# 3__schdoc.net
KiCad netlist of a schematic drawn in Altium Designer
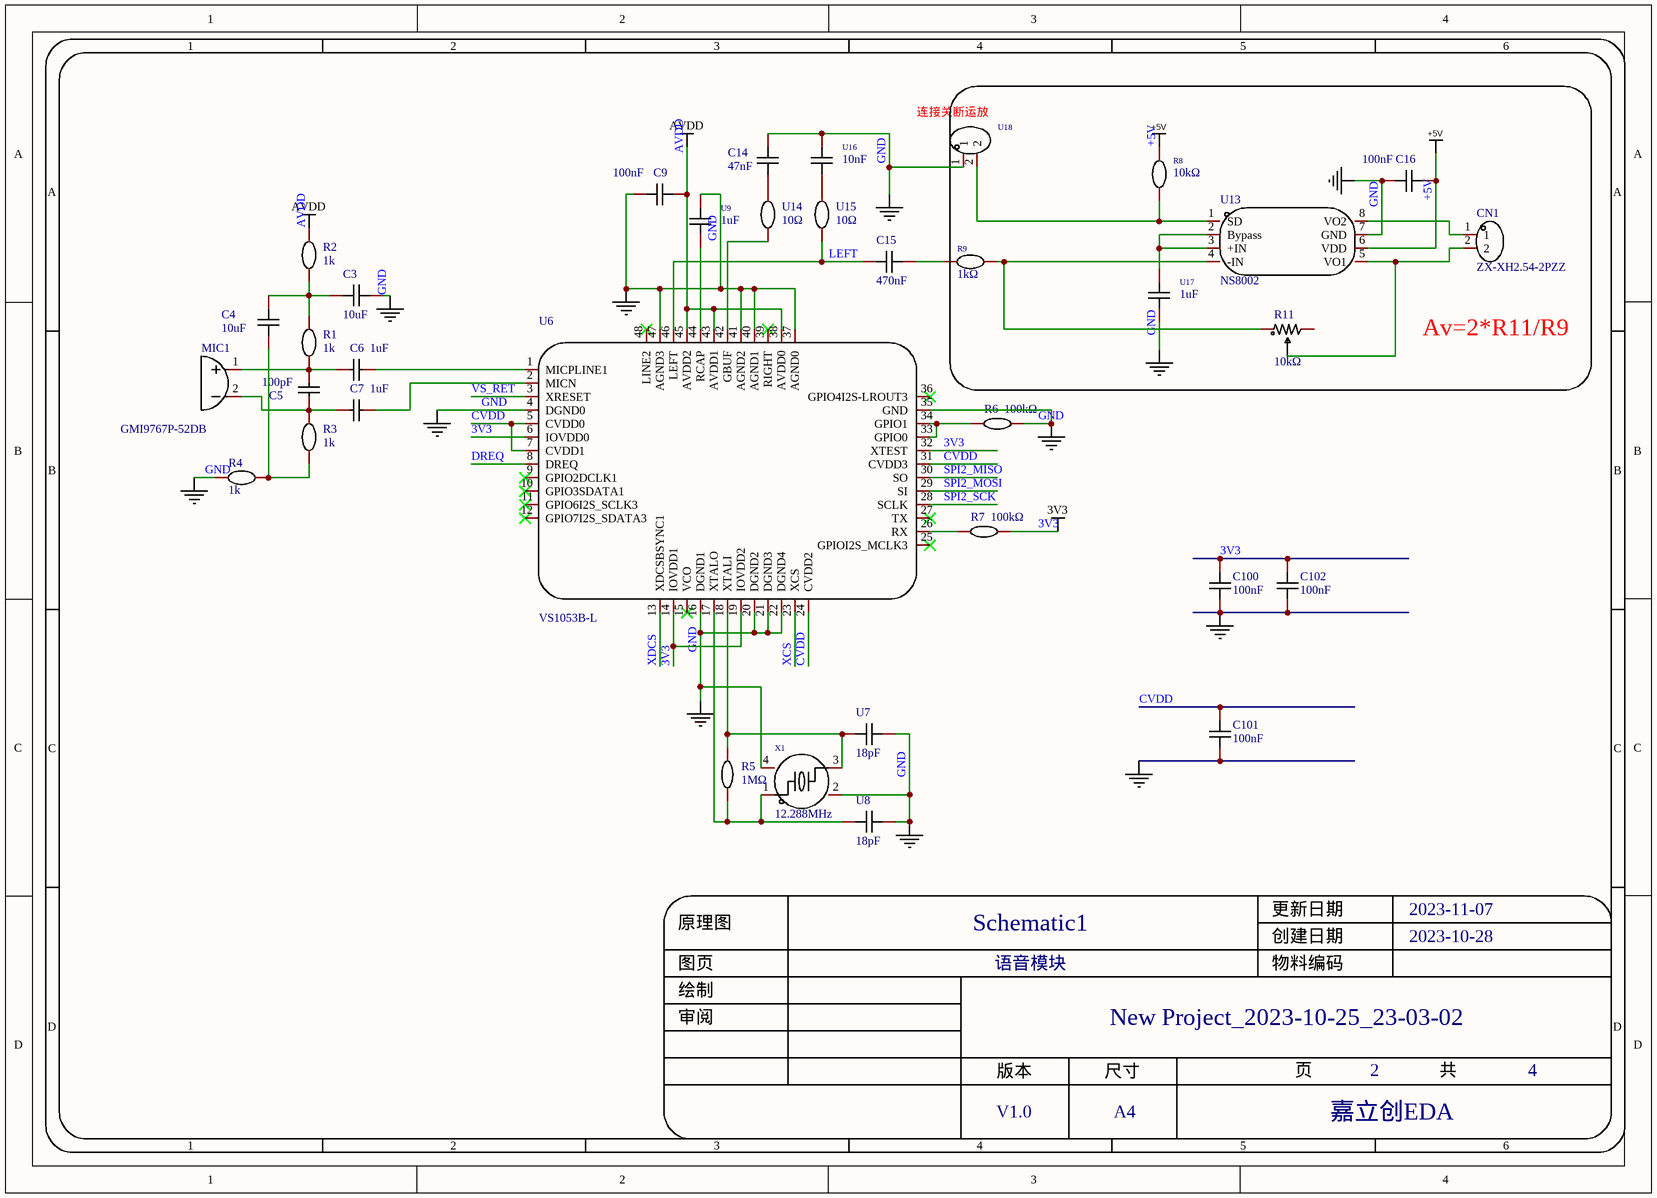
[diagram p0: 3_语音模块.schdoc.schdoc]

(export (version "E")
  (design (tool "Eeschema 10.0.6"))
  (components
    (comp (ref "C3")
      (value "10uF")
      (footprint "C0603")
      (description "容值:10uF;精度:±20%;额定电压:25V;材质(温度系数):X5R;")
      (fields
        (field (name "NAME") "10uF")
        (field (name "MANUFACTURER") "SAMSUNG(三星)")
        (field (name "MANUFACTURER PART") "CL10A106MA8NRNC")
      )
      (libsource (lib "altium-import") (part "root_0_CL10A106MA8NRNC_"))
    )
    (comp (ref "C4")
      (value "10uF")
      (footprint "C0603")
      (description "容值:10uF;精度:±20%;额定电压:25V;材质(温度系数):X5R;")
      (fields
        (field (name "NAME") "10uF")
        (field (name "MANUFACTURER") "SAMSUNG(三星)")
        (field (name "MANUFACTURER PART") "CL10A106MA8NRNC")
      )
      (libsource (lib "altium-import") (part "root_1_CL10A106MA8NRNC_"))
    )
    (comp (ref "C5")
      (value "100pF")
      (footprint "C0603")
      (description "容值:100pF;精度:±5%;额定电压:50V;材质(温度系数):C0G;")
      (fields
        (field (name "NAME") "100pF")
        (field (name "MANUFACTURER") "SAMSUNG(三星)")
        (field (name "MANUFACTURER PART") "CL10C101JB8NNNC")
      )
      (libsource (lib "altium-import") (part "root_1_CL10C101JB8NNNC_"))
    )
    (comp (ref "C6")
      (value "1uF")
      (footprint "C0603")
      (description "容值:1uF;精度:±10%;额定电压:50V;材质(温度系数):X5R;")
      (fields
        (field (name "NAME") "1uF")
        (field (name "MANUFACTURER") "SAMSUNG(三星)")
        (field (name "MANUFACTURER PART") "CL10A105KB8NNNC")
      )
      (libsource (lib "altium-import") (part "root_0_CL10A105KB8NNNC_"))
    )
    (comp (ref "C7")
      (value "1uF")
      (footprint "C0603")
      (description "容值:1uF;精度:±10%;额定电压:50V;材质(温度系数):X5R;")
      (fields
        (field (name "NAME") "1uF")
        (field (name "MANUFACTURER") "SAMSUNG(三星)")
        (field (name "MANUFACTURER PART") "CL10A105KB8NNNC")
      )
      (libsource (lib "altium-import") (part "root_0_CL10A105KB8NNNC_"))
    )
    (comp (ref "C9")
      (value "100nF")
      (footprint "C0603")
      (description "容值:100nF;精度:±20%;额定电压:50V;材质(温度系数):X8R;")
      (fields
        (field (name "NAME") "100nF")
        (field (name "MANUFACTURER") "TDK")
        (field (name "MANUFACTURER PART") "CGA3E3X8R1H104M080AE")
      )
      (libsource (lib "altium-import") (part "root_2_CGA3E3X8R1H104M080AE_"))
    )
    (comp (ref "C14")
      (value "47nF")
      (footprint "C0603")
      (description "容值:47nF;额定电压:50V;材质(温度系数):X8R;")
      (fields
        (field (name "NAME") "47nF")
        (field (name "MANUFACTURER") "TDK")
        (field (name "MANUFACTURER PART") "C1608X8R1H473K080AA")
      )
      (libsource (lib "altium-import") (part "root_1_C1608X8R1H473K080AA_"))
    )
    (comp (ref "C15")
      (value "470nF")
      (footprint "C0805")
      (description "容值:470nF;精度:±10%;额定电压:100V;材质(温度系数):X7R;")
      (fields
        (field (name "NAME") "470nF")
        (field (name "MANUFACTURER") "YAGEO(国巨)")
        (field (name "MANUFACTURER PART") "CC0805KKX7R0BB474")
      )
      (libsource (lib "altium-import") (part "root_0_CC0805KKX7R0BB474_"))
    )
    (comp (ref "C16")
      (value "100nF")
      (footprint "C0603")
      (description "容值:100nF;精度:±20%;额定电压:50V;材质(温度系数):X8R;")
      (fields
        (field (name "NAME") "100nF")
        (field (name "MANUFACTURER") "TDK")
        (field (name "MANUFACTURER PART") "CGA3E3X8R1H104M080AE")
      )
      (libsource (lib "altium-import") (part "root_2_CGA3E3X8R1H104M080AE_"))
    )
    (comp (ref "C100")
      (value "100nF")
      (footprint "C0603")
      (description "容值:100nF;精度:±20%;额定电压:50V;材质(温度系数):X8R;")
      (fields
        (field (name "NAME") "100nF")
        (field (name "MANUFACTURER") "TDK")
        (field (name "MANUFACTURER PART") "CGA3E3X8R1H104M080AE")
      )
      (libsource (lib "altium-import") (part "root_3_CGA3E3X8R1H104M080AE_"))
    )
    (comp (ref "C101")
      (value "100nF")
      (footprint "C0603")
      (description "容值:100nF;精度:±20%;额定电压:50V;材质(温度系数):X8R;")
      (fields
        (field (name "NAME") "100nF")
        (field (name "MANUFACTURER") "TDK")
        (field (name "MANUFACTURER PART") "CGA3E3X8R1H104M080AE")
      )
      (libsource (lib "altium-import") (part "root_3_CGA3E3X8R1H104M080AE_"))
    )
    (comp (ref "C102")
      (value "100nF")
      (footprint "C0603")
      (description "容值:100nF;精度:±20%;额定电压:50V;材质(温度系数):X8R;")
      (fields
        (field (name "NAME") "100nF")
        (field (name "MANUFACTURER") "TDK")
        (field (name "MANUFACTURER PART") "CGA3E3X8R1H104M080AE")
      )
      (libsource (lib "altium-import") (part "root_3_CGA3E3X8R1H104M080AE_"))
    )
    (comp (ref "CN1")
      (value "ZX-XH2.54-2PZZ")
      (footprint "CONN-TH_2P-P2.50_HX25003-2A")
      (fields (field (name "NAME") "ZX-XH2.54-2PZZ") (field (name "MANUFACTURER") "Megastar(兆星)"))
      (libsource (lib "altium-import") (part "root_0_ZX-XH2.54-2PZZ_"))
    )
    (comp (ref "MIC1")
      (value "GMI9767P-52DB")
      (footprint "MIC-TH_BD9.7-P2.54-D0.8-L-FD")
      (fields (field (name "NAME") "GMI9767P-52DB") (field (name "MANUFACTURER") "INGHAi(赢海)"))
      (libsource (lib "altium-import") (part "root_3_mirrored_GMI9767P-52DB_"))
    )
    (comp (ref "R1")
      (value "1k")
      (footprint "R0603")
      (fields (field (name "NAME") "1k"))
      (libsource (lib "altium-import") (part "root_1_1k_"))
    )
    (comp (ref "R2")
      (value "1k")
      (footprint "R0603")
      (fields (field (name "NAME") "1k"))
      (libsource (lib "altium-import") (part "root_1_1k_"))
    )
    (comp (ref "R3")
      (value "1k")
      (footprint "R0603")
      (fields (field (name "NAME") "1k"))
      (libsource (lib "altium-import") (part "root_1_1k_"))
    )
    (comp (ref "R4")
      (value "1k")
      (footprint "R0603")
      (fields (field (name "NAME") "1k"))
      (libsource (lib "altium-import") (part "root_2_1k_"))
    )
    (comp (ref "R5")
      (value "1MΩ")
      (footprint "R0603")
      (description "电阻类型:厚膜电阻;阻值:1MΩ;精度:±1%;功率:100mW;温度系数:±100ppm/℃;")
      (fields
        (field (name "NAME") "1MΩ")
        (field (name "MANUFACTURER") "UNI-ROYAL(厚声)")
        (field (name "MANUFACTURER PART") "0603WAF1004T5E")
      )
      (libsource (lib "altium-import") (part "root_1_0603WAF1004T5E_"))
    )
    (comp (ref "R6")
      (value "100kΩ")
      (footprint "R0603")
      (description "电阻类型:厚膜电阻;阻值:100kΩ;精度:±1%;功率:100mW;温度系数:±100ppm/℃;")
      (fields
        (field (name "NAME") "100kΩ")
        (field (name "MANUFACTURER") "PANASONIC(松下)")
        (field (name "MANUFACTURER PART") "ERJ3EKF1003V")
      )
      (libsource (lib "altium-import") (part "root_0_ERJ3EKF1003V_"))
    )
    (comp (ref "R7")
      (value "100kΩ")
      (footprint "R0603")
      (description "电阻类型:厚膜电阻;阻值:100kΩ;精度:±1%;功率:100mW;温度系数:±100ppm/℃;")
      (fields
        (field (name "NAME") "100kΩ")
        (field (name "MANUFACTURER") "PANASONIC(松下)")
        (field (name "MANUFACTURER PART") "ERJ3EKF1003V")
      )
      (libsource (lib "altium-import") (part "root_0_ERJ3EKF1003V_"))
    )
    (comp (ref "R8")
      (value "10kΩ")
      (footprint "R0603")
      (description "阻值:10kΩ;精度:±5%;")
      (fields
        (field (name "NAME") "10kΩ")
        (field (name "MANUFACTURER") "VO(翔胜)")
        (field (name "MANUFACTURER PART") "SCR0603J10K")
      )
      (libsource (lib "altium-import") (part "root_1_SCR0603J10K_"))
    )
    (comp (ref "R9")
      (value "1kΩ")
      (footprint "R0603")
      (description "阻值:1kΩ;精度:±1%;")
      (fields
        (field (name "NAME") "1kΩ")
        (field (name "MANUFACTURER") "VO(翔胜)")
        (field (name "MANUFACTURER PART") "SCR0603F1K")
      )
      (libsource (lib "altium-import") (part "root_0_SCR0603F1K_"))
    )
    (comp (ref "R11")
      (value "10kΩ")
      (footprint "RES-ADJ-TH_3362P")
      (description "阻值:10kΩ;精度:±10%;")
      (fields
        (field (name "NAME") "10kΩ")
        (field (name "MANUFACTURER") "BOCHEN(博晨)")
        (field (name "MANUFACTURER PART") "3362P-1-103")
      )
      (libsource (lib "altium-import") (part "root_2_3362P-1-103_"))
    )
    (comp (ref "U6")
      (value "VS1053B-L")
      (footprint "LQFP-48_L7.0-W7.0-P0.50-LS9.0-BL")
      (description "MP3芯片")
      (fields (field (name "NAME") "VS1053B-L") (field (name "MANUFACTURER") "VLSI"))
      (libsource (lib "altium-import") (part "root_0_VS1053B-L_"))
    )
    (comp (ref "U7")
      (value "18pF")
      (footprint "C0603")
      (description "容值:18pF;精度:±5%;额定电压:100V;材质(温度系数):CH;")
      (fields
        (field (name "NAME") "18pF")
        (field (name "MANUFACTURER") "TDK")
        (field (name "MANUFACTURER PART") "C1608CH2A180J080AA")
      )
      (libsource (lib "altium-import") (part "root_0_C1608CH2A180J080AA_"))
    )
    (comp (ref "U8")
      (value "18pF")
      (footprint "C0603")
      (description "容值:18pF;精度:±5%;额定电压:100V;材质(温度系数):CH;")
      (fields
        (field (name "NAME") "18pF")
        (field (name "MANUFACTURER") "TDK")
        (field (name "MANUFACTURER PART") "C1608CH2A180J080AA")
      )
      (libsource (lib "altium-import") (part "root_0_C1608CH2A180J080AA_"))
    )
    (comp (ref "U9")
      (value "1uF")
      (footprint "C0603")
      (description "容值:1uF;精度:±20%;额定电压:35V;材质(温度系数):X5R;")
      (fields
        (field (name "NAME") "1uF")
        (field (name "MANUFACTURER") "TDK")
        (field (name "MANUFACTURER PART") "CGA3E3X5R1V105M080AB")
      )
      (libsource (lib "altium-import") (part "root_1_CGA3E3X5R1V105M080AB_"))
    )
    (comp (ref "U13")
      (value "NS8002")
      (footprint "SOP-8_L4.9-W3.9-P1.27-LS6.0-BL")
      (description "音频功率放大器的类型:Class AB;输出类型:-;输出功率:1.8W x 1 @ 4Ω;工作电压:3V ~ 5.25V;")
      (fields (field (name "NAME") "NS8002") (field (name "MANUFACTURER") "Nsiway(纳芯威)"))
      (libsource (lib "altium-import") (part "root_0_NS8002_"))
    )
    (comp (ref "U14")
      (value "10Ω")
      (footprint "R0603")
      (description "电阻类型:薄膜电阻;阻值:10Ω;精度:±0.1%;功率:500mW;")
      (fields
        (field (name "NAME") "10Ω")
        (field (name "MANUFACTURER") "VISHAY(威世)")
        (field (name "MANUFACTURER PART") "PCAN0603E10R0BST5")
      )
      (libsource (lib "altium-import") (part "root_1_PCAN0603E10R0BST5_"))
    )
    (comp (ref "U15")
      (value "10Ω")
      (footprint "R0603")
      (description "电阻类型:薄膜电阻;阻值:10Ω;精度:±0.1%;功率:500mW;")
      (fields
        (field (name "NAME") "10Ω")
        (field (name "MANUFACTURER") "VISHAY(威世)")
        (field (name "MANUFACTURER PART") "PCAN0603E10R0BST5")
      )
      (libsource (lib "altium-import") (part "root_1_PCAN0603E10R0BST5_"))
    )
    (comp (ref "U16")
      (value "10nF")
      (footprint "C0603")
      (description "容值:10nF;精度:±10%;额定电压:100V;材质(温度系数):X8R;")
      (fields
        (field (name "NAME") "10nF")
        (field (name "MANUFACTURER") "TDK")
        (field (name "MANUFACTURER PART") "C1608X8R2A103K080AA")
      )
      (libsource (lib "altium-import") (part "root_1_C1608X8R2A103K080AA_"))
    )
    (comp (ref "U17")
      (value "1uF")
      (footprint "C0603")
      (description "容值:1uF;精度:±20%;额定电压:35V;材质(温度系数):X5R;")
      (fields
        (field (name "NAME") "1uF")
        (field (name "MANUFACTURER") "TDK")
        (field (name "MANUFACTURER PART") "CGA3E3X5R1V105M080AB")
      )
      (libsource (lib "altium-import") (part "root_1_CGA3E3X5R1V105M080AB_"))
    )
    (comp (ref "U18")
      (value "PZ200-1-02-Z-C")
      (footprint "HDR-TH_2P-P2.00-V-M-3")
      (fields (field (name "MANUFACTURER") "HCTL(华灿天禄)"))
      (libsource (lib "altium-import") (part "root_1_PZ200-1-02-Z-C_"))
    )
    (comp (ref "X1")
      (value "12.288MHz")
      (footprint "CRYSTAL-SMD_4P-L3.2-W2.5-BL")
      (description "频率:12.288MHz;频率公差:±10ppm;负载电容:20pF;")
      (fields
        (field (name "NAME") "12.288MHz")
        (field (name "MANUFACTURER") "SCTF(星通时频)")
        (field (name "MANUFACTURER PART") "SX3B12.288F2010F30")
      )
      (libsource (lib "altium-import") (part "root_0_SX3B12.288F2010F30_"))
    )
  )
  (nets
    (net (code "1") (name "+5V") (class "Default")
      (node (ref "C16") (pin "1") (pinfunction "1_1") (pintype "passive"))
      (node (ref "R8") (pin "2") (pinfunction "2_2") (pintype "passive"))
      (node (ref "U13") (pin "6") (pinfunction "VDD_6") (pintype "passive"))
    )
    (net (code "2") (name "/CVDD") (class "Default")
      (node (ref "C101") (pin "1") (pinfunction "1_1") (pintype "passive"))
      (node (ref "U6") (pin "24") (pinfunction "CVDD2_24") (pintype "passive"))
      (node (ref "U6") (pin "31") (pinfunction "CVDD3_31") (pintype "passive"))
      (node (ref "U6") (pin "5") (pinfunction "CVDD0_5") (pintype "passive"))
      (node (ref "U6") (pin "7") (pinfunction "CVDD1_7") (pintype "passive"))
    )
    (net (code "3") (name "/DREQ") (class "Default")
      (node (ref "U6") (pin "8") (pinfunction "DREQ_8") (pintype "passive"))
    )
    (net (code "4") (name "/GND") (class "Default")
      (node (ref "C100") (pin "2") (pinfunction "2_2") (pintype "passive"))
      (node (ref "C101") (pin "2") (pinfunction "2_2") (pintype "passive"))
      (node (ref "C102") (pin "2") (pinfunction "2_2") (pintype "passive"))
      (node (ref "C14") (pin "2") (pinfunction "2_2") (pintype "passive"))
      (node (ref "C16") (pin "2") (pinfunction "2_2") (pintype "passive"))
      (node (ref "C3") (pin "2") (pinfunction "2_2") (pintype "passive"))
      (node (ref "C9") (pin "2") (pinfunction "2_2") (pintype "passive"))
      (node (ref "R4") (pin "2") (pinfunction "2_2") (pintype "passive"))
      (node (ref "R6") (pin "2") (pinfunction "2_2") (pintype "passive"))
      (node (ref "U13") (pin "7") (pinfunction "GND_7") (pintype "passive"))
      (node (ref "U16") (pin "2") (pinfunction "2_2") (pintype "passive"))
      (node (ref "U17") (pin "1") (pinfunction "1_1") (pintype "passive"))
      (node (ref "U18") (pin "1") (pinfunction "1_1") (pintype "passive"))
      (node (ref "U6") (pin "16") (pinfunction "DGND1_16") (pintype "passive"))
      (node (ref "U6") (pin "20") (pinfunction "DGND2_20") (pintype "passive"))
      (node (ref "U6") (pin "21") (pinfunction "DGND3_21") (pintype "passive"))
      (node (ref "U6") (pin "22") (pinfunction "DGND4_22") (pintype "passive"))
      (node (ref "U6") (pin "35") (pinfunction "GND_35") (pintype "passive"))
      (node (ref "U6") (pin "37") (pinfunction "AGND0_37") (pintype "passive"))
      (node (ref "U6") (pin "4") (pinfunction "DGND0_4") (pintype "passive"))
      (node (ref "U6") (pin "40") (pinfunction "AGND1_40") (pintype "passive"))
      (node (ref "U6") (pin "41") (pinfunction "AGND2_41") (pintype "passive"))
      (node (ref "U6") (pin "47") (pinfunction "AGND3_47") (pintype "passive"))
      (node (ref "U7") (pin "2") (pinfunction "2_2") (pintype "passive"))
      (node (ref "U8") (pin "2") (pinfunction "2_2") (pintype "passive"))
      (node (ref "U9") (pin "2") (pinfunction "2_2") (pintype "passive"))
      (node (ref "X1") (pin "2") (pinfunction "GND_2") (pintype "passive"))
      (node (ref "X1") (pin "4") (pinfunction "GND_4") (pintype "passive"))
    )
    (net (code "5") (name "/LEFT") (class "Default")
      (node (ref "C15") (pin "1") (pinfunction "1_1") (pintype "passive"))
      (node (ref "U15") (pin "1") (pinfunction "1_1") (pintype "passive"))
      (node (ref "U6") (pin "46") (pinfunction "LEFT_46") (pintype "passive"))
    )
    (net (code "6") (name "/SPI2_MISO") (class "Default")
      (node (ref "U6") (pin "30") (pinfunction "SO_30") (pintype "passive"))
    )
    (net (code "7") (name "/SPI2_MOSI") (class "Default")
      (node (ref "U6") (pin "29") (pinfunction "SI_29") (pintype "passive"))
    )
    (net (code "8") (name "/SPI2_SCK") (class "Default")
      (node (ref "U6") (pin "28") (pinfunction "SCLK_28") (pintype "passive"))
    )
    (net (code "9") (name "/VS_RET") (class "Default")
      (node (ref "U6") (pin "3") (pinfunction "XRESET_3") (pintype "passive"))
    )
    (net (code "10") (name "/XCS") (class "Default")
      (node (ref "U6") (pin "23") (pinfunction "XCS_23") (pintype "passive"))
    )
    (net (code "11") (name "/XDCS") (class "Default")
      (node (ref "U6") (pin "13") (pinfunction "XDCSBSYNC1_13") (pintype "passive"))
    )
    (net (code "12") (name "3V3") (class "Default")
      (node (ref "C100") (pin "1") (pinfunction "1_1") (pintype "passive"))
      (node (ref "C102") (pin "1") (pinfunction "1_1") (pintype "passive"))
      (node (ref "R7") (pin "2") (pinfunction "2_2") (pintype "passive"))
      (node (ref "U6") (pin "14") (pinfunction "IOVDD1_14") (pintype "passive"))
      (node (ref "U6") (pin "19") (pinfunction "IOVDD2_19") (pintype "passive"))
      (node (ref "U6") (pin "32") (pinfunction "XTEST_32") (pintype "passive"))
      (node (ref "U6") (pin "6") (pinfunction "IOVDD0_6") (pintype "passive"))
    )
    (net (code "13") (name "AVDD") (class "Default")
      (node (ref "C9") (pin "1") (pinfunction "1_1") (pintype "passive"))
      (node (ref "R2") (pin "2") (pinfunction "2_2") (pintype "passive"))
      (node (ref "U6") (pin "38") (pinfunction "AVDD0_38") (pintype "passive"))
      (node (ref "U6") (pin "43") (pinfunction "AVDD1_43") (pintype "passive"))
      (node (ref "U6") (pin "45") (pinfunction "AVDD2_45") (pintype "passive"))
    )
    (net (code "14") (name "Net-(C3-Pad1)") (class "Default")
      (node (ref "C3") (pin "1") (pinfunction "1_1") (pintype "passive"))
      (node (ref "C4") (pin "2") (pinfunction "2_2") (pintype "passive"))
      (node (ref "R1") (pin "2") (pinfunction "2_2") (pintype "passive"))
      (node (ref "R2") (pin "1") (pinfunction "1_1") (pintype "passive"))
    )
    (net (code "15") (name "Net-(C4-Pad1)") (class "Default")
      (node (ref "C4") (pin "1") (pinfunction "1_1") (pintype "passive"))
      (node (ref "R3") (pin "1") (pinfunction "1_1") (pintype "passive"))
      (node (ref "R4") (pin "1") (pinfunction "1_1") (pintype "passive"))
    )
    (net (code "16") (name "Net-(C5-Pad1)") (class "Default")
      (node (ref "C5") (pin "1") (pinfunction "1_1") (pintype "passive"))
      (node (ref "C7") (pin "1") (pinfunction "1_1") (pintype "passive"))
      (node (ref "MIC1") (pin "2") (pinfunction "2_2") (pintype "passive"))
      (node (ref "R3") (pin "2") (pinfunction "2_2") (pintype "passive"))
    )
    (net (code "17") (name "Net-(C5-Pad2)") (class "Default")
      (node (ref "C5") (pin "2") (pinfunction "2_2") (pintype "passive"))
      (node (ref "C6") (pin "1") (pinfunction "1_1") (pintype "passive"))
      (node (ref "MIC1") (pin "1") (pinfunction "1_1") (pintype "passive"))
      (node (ref "R1") (pin "1") (pinfunction "1_1") (pintype "passive"))
    )
    (net (code "18") (name "Net-(C14-Pad1)") (class "Default")
      (node (ref "C14") (pin "1") (pinfunction "1_1") (pintype "passive"))
      (node (ref "U14") (pin "2") (pinfunction "2_2") (pintype "passive"))
    )
    (net (code "19") (name "Net-(C15-Pad2)") (class "Default")
      (node (ref "C15") (pin "2") (pinfunction "2_2") (pintype "passive"))
      (node (ref "R9") (pin "1") (pinfunction "1_1") (pintype "passive"))
    )
    (net (code "20") (name "Net-(U6-GBUF)") (class "Default")
      (node (ref "U14") (pin "1") (pinfunction "1_1") (pintype "passive"))
      (node (ref "U6") (pin "42") (pinfunction "GBUF_42") (pintype "passive"))
    )
    (net (code "21") (name "Net-(U6-GPIO0)") (class "Default")
      (node (ref "R6") (pin "1") (pinfunction "1_1") (pintype "passive"))
      (node (ref "U6") (pin "33") (pinfunction "GPIO0_33") (pintype "passive"))
      (node (ref "U6") (pin "34") (pinfunction "GPIO1_34") (pintype "passive"))
    )
    (net (code "22") (name "Net-(U6-MICN)") (class "Default")
      (node (ref "C7") (pin "2") (pinfunction "2_2") (pintype "passive"))
      (node (ref "U6") (pin "2") (pinfunction "MICN_2") (pintype "passive"))
    )
    (net (code "23") (name "Net-(U6-MICPLINE1)") (class "Default")
      (node (ref "C6") (pin "2") (pinfunction "2_2") (pintype "passive"))
      (node (ref "U6") (pin "1") (pinfunction "MICPLINE1_1") (pintype "passive"))
    )
    (net (code "24") (name "Net-(U6-RCAP)") (class "Default")
      (node (ref "U6") (pin "44") (pinfunction "RCAP_44") (pintype "passive"))
      (node (ref "U9") (pin "1") (pinfunction "1_1") (pintype "passive"))
    )
    (net (code "25") (name "Net-(U6-RX)") (class "Default")
      (node (ref "R7") (pin "1") (pinfunction "1_1") (pintype "passive"))
      (node (ref "U6") (pin "26") (pinfunction "RX_26") (pintype "passive"))
    )
    (net (code "26") (name "Net-(U6-XTALI)") (class "Default")
      (node (ref "R5") (pin "2") (pinfunction "2_2") (pintype "passive"))
      (node (ref "U6") (pin "18") (pinfunction "XTALI_18") (pintype "passive"))
      (node (ref "U7") (pin "1") (pinfunction "1_1") (pintype "passive"))
      (node (ref "X1") (pin "3") (pinfunction "3_3") (pintype "passive"))
    )
    (net (code "27") (name "Net-(U6-XTALO)") (class "Default")
      (node (ref "R5") (pin "1") (pinfunction "1_1") (pintype "passive"))
      (node (ref "U6") (pin "17") (pinfunction "XTALO_17") (pintype "passive"))
      (node (ref "U8") (pin "1") (pinfunction "1_1") (pintype "passive"))
      (node (ref "X1") (pin "1") (pinfunction "1_1") (pintype "passive"))
    )
    (net (code "28") (name "Net-(U13-+IN)") (class "Default")
      (node (ref "U13") (pin "2") (pinfunction "Bypass_2") (pintype "passive"))
      (node (ref "U13") (pin "3") (pinfunction "+IN_3") (pintype "passive"))
      (node (ref "U17") (pin "2") (pinfunction "2_2") (pintype "passive"))
    )
    (net (code "29") (name "Net-(U13--IN)") (class "Default")
      (node (ref "R11") (pin "1") (pinfunction "1_1") (pintype "passive"))
      (node (ref "R9") (pin "2") (pinfunction "2_2") (pintype "passive"))
      (node (ref "U13") (pin "4") (pinfunction "-IN_4") (pintype "passive"))
    )
    (net (code "30") (name "Net-(U13-SD)") (class "Default")
      (node (ref "R8") (pin "1") (pinfunction "1_1") (pintype "passive"))
      (node (ref "U13") (pin "1") (pinfunction "SD_1") (pintype "passive"))
      (node (ref "U18") (pin "2") (pinfunction "2_2") (pintype "passive"))
    )
    (net (code "31") (name "Net-(U13-VO1)") (class "Default")
      (node (ref "CN1") (pin "2") (pinfunction "2_2") (pintype "passive"))
      (node (ref "R11") (pin "2") (pinfunction "2_2") (pintype "passive"))
      (node (ref "U13") (pin "5") (pinfunction "VO1_5") (pintype "passive"))
    )
    (net (code "32") (name "Net-(U13-VO2)") (class "Default")
      (node (ref "CN1") (pin "1") (pinfunction "1_1") (pintype "passive"))
      (node (ref "U13") (pin "8") (pinfunction "VO2_8") (pintype "passive"))
    )
    (net (code "33") (name "Net-(U15-Pad2)") (class "Default")
      (node (ref "U15") (pin "2") (pinfunction "2_2") (pintype "passive"))
      (node (ref "U16") (pin "1") (pinfunction "1_1") (pintype "passive"))
    )
    (net (code "34") (name "unconnected-(R11-Pad3)") (class "Default")
      (node (ref "R11") (pin "3") (pinfunction "3_3") (pintype "passive"))
    )
    (net (code "35") (name "unconnected-(U6-GPIO2DCLK1-Pad9)") (class "Default")
      (node (ref "U6") (pin "9") (pinfunction "GPIO2DCLK1_9") (pintype "passive+no_connect"))
    )
    (net (code "36") (name "unconnected-(U6-GPIO3SDATA1-Pad10)") (class "Default")
      (node (ref "U6") (pin "10") (pinfunction "GPIO3SDATA1_10") (pintype "passive+no_connect"))
    )
    (net (code "37") (name "unconnected-(U6-GPIO4I2S-LROUT3-Pad36)") (class "Default")
      (node (ref "U6") (pin "36") (pinfunction "GPIO4I2S-LROUT3_36") (pintype "passive+no_connect"))
    )
    (net (code "38") (name "unconnected-(U6-GPIO6I2S_SCLK3-Pad11)") (class "Default")
      (node (ref "U6") (pin "11") (pinfunction "GPIO6I2S_SCLK3_11") (pintype "passive+no_connect"))
    )
    (net (code "39") (name "unconnected-(U6-GPIO7I2S_SDATA3-Pad12)") (class "Default")
      (node (ref "U6") (pin "12") (pinfunction "GPIO7I2S_SDATA3_12") (pintype "passive+no_connect"))
    )
    (net (code "40") (name "unconnected-(U6-GPIOI2S_MCLK3-Pad25)") (class "Default")
      (node (ref "U6") (pin "25") (pinfunction "GPIOI2S_MCLK3_25") (pintype "passive+no_connect"))
    )
    (net (code "41") (name "unconnected-(U6-LINE2-Pad48)") (class "Default")
      (node (ref "U6") (pin "48") (pinfunction "LINE2_48") (pintype "passive+no_connect"))
    )
    (net (code "42") (name "unconnected-(U6-RIGHT-Pad39)") (class "Default")
      (node (ref "U6") (pin "39") (pinfunction "RIGHT_39") (pintype "passive+no_connect"))
    )
    (net (code "43") (name "unconnected-(U6-TX-Pad27)") (class "Default")
      (node (ref "U6") (pin "27") (pinfunction "TX_27") (pintype "passive+no_connect"))
    )
    (net (code "44") (name "unconnected-(U6-VCO-Pad15)") (class "Default")
      (node (ref "U6") (pin "15") (pinfunction "VCO_15") (pintype "passive+no_connect"))
    )
  )
)
